# SCH_GROUP-8-WORK.net
KiCad netlist of a schematic drawn in EasyEDA
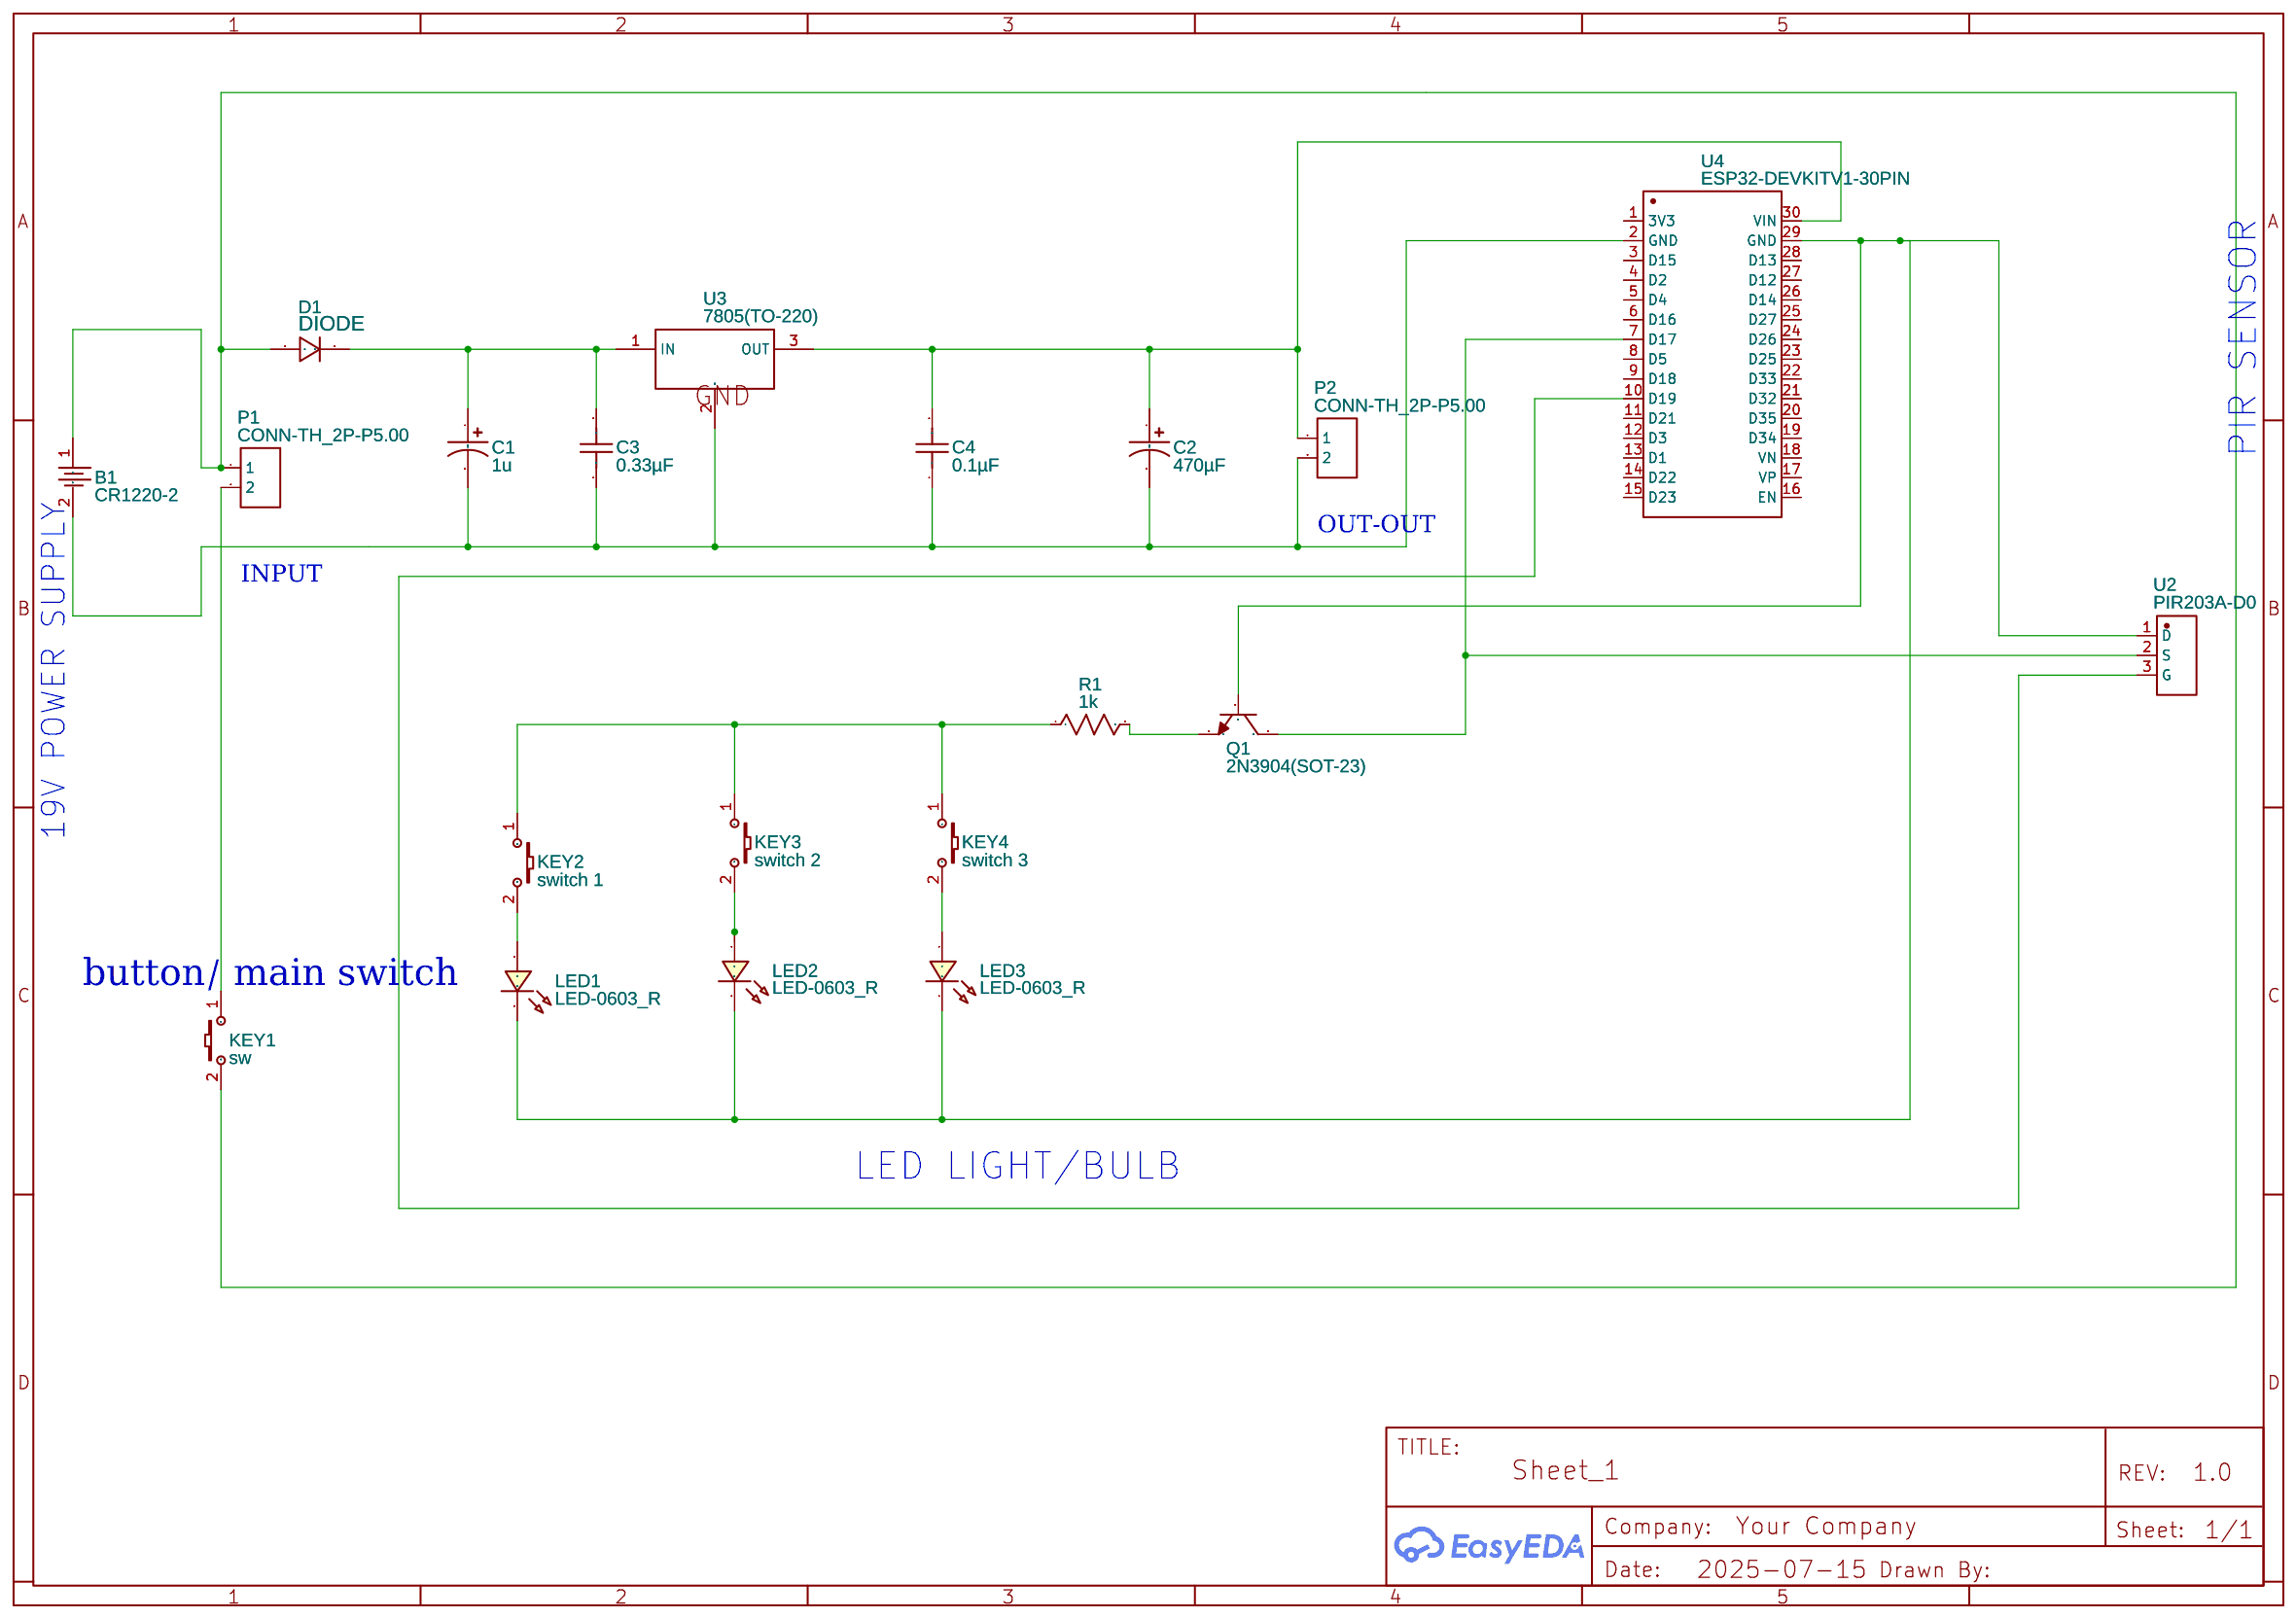
[diagram p0: schematic sheet]

(export (version "E")
  (design (tool "Eeschema 10.0.6"))
  (components
    (comp (ref "B1")
      (value "CR1220-2")
      (fields (field (name "Manufacturer") "Q&J"))
      (libsource (lib "") (part "CR1220-2"))
    )
    (comp (ref "C1") (value "1u") (libsource (lib "") (part "CE_TH_D3.0×F1.5_US")))
    (comp (ref "C2") (value "470µF") (libsource (lib "") (part "CE_TH_D3.0×F1.5_US")))
    (comp (ref "C3") (value "0.33µF") (libsource (lib "") (part "C_RAD-0.1_US")))
    (comp (ref "C4") (value "0.1µF") (libsource (lib "") (part "C_RAD-0.1_US")))
    (comp (ref "D1")
      (value "DIODE")
      (fields (field (name "Manufacturer Part") "1N4007W") (field (name "Manufacturer") "BLUE ROCKET"))
      (libsource (lib "") (part "1N4007W"))
    )
    (comp (ref "KEY1")
      (value "sw")
      (fields (field (name "Manufacturer Part") "K2-1107ST-A4SW-06"))
      (libsource (lib "") (part "K2-3.6×6.1_SMD_1"))
    )
    (comp (ref "KEY2")
      (value "switch 1")
      (fields (field (name "Manufacturer Part") "K2-1107ST-A4SW-06"))
      (libsource (lib "") (part "K2-3.6×6.1_SMD"))
    )
    (comp (ref "KEY3")
      (value "switch 2")
      (fields (field (name "Manufacturer Part") "K2-1107ST-A4SW-06"))
      (libsource (lib "") (part "K2-3.6×6.1_SMD"))
    )
    (comp (ref "KEY4")
      (value "switch 3")
      (fields (field (name "Manufacturer Part") "K2-1107ST-A4SW-06"))
      (libsource (lib "") (part "K2-3.6×6.1_SMD"))
    )
    (comp (ref "LED1")
      (value "LED-0603_R")
      (fields
        (field (name "Manufacturer Part") "19-217/R6C-AL1M2VY/3T")
        (field (name "Manufacturer") "EVERLIGHT(台湾亿光)")
      )
      (libsource (lib "") (part "LED-0603_R"))
    )
    (comp (ref "LED2")
      (value "LED-0603_R")
      (fields
        (field (name "Manufacturer Part") "19-217/R6C-AL1M2VY/3T")
        (field (name "Manufacturer") "EVERLIGHT(台湾亿光)")
      )
      (libsource (lib "") (part "LED-0603_R"))
    )
    (comp (ref "LED3")
      (value "LED-0603_R")
      (fields
        (field (name "Manufacturer Part") "19-217/R6C-AL1M2VY/3T")
        (field (name "Manufacturer") "EVERLIGHT(台湾亿光)")
      )
      (libsource (lib "") (part "LED-0603_R"))
    )
    (comp (ref "P1") (value "CONN-TH_2P-P5.00") (libsource (lib "") (part "CONN-TH_2P-P5.00")))
    (comp (ref "P2") (value "CONN-TH_2P-P5.00") (libsource (lib "") (part "CONN-TH_2P-P5.00")))
    (comp (ref "Q1")
      (value "2N3904(SOT-23)")
      (fields (field (name "Manufacturer Part") "2n3904S-RTK/PS") (field (name "Manufacturer") "KEC"))
      (libsource (lib "") (part "2N3904(SOT-23)"))
    )
    (comp (ref "R1") (value "1k") (libsource (lib "") (part "R_0603_US")))
    (comp (ref "U2")
      (value "PIR203A-D0")
      (fields (field (name "Manufacturer") "NEWOPTO(鑫永诚光电)"))
      (libsource (lib "") (part "PIR203A-D0"))
    )
    (comp (ref "U3")
      (value "7805(TO-220)")
      (fields
        (field (name "Manufacturer Part") "L7805CV-DG")
        (field (name "Manufacturer") "STMicroelectronics")
      )
      (libsource (lib "") (part "7805(TO-220)"))
    )
    (comp (ref "U4")
      (value "ESP32-DEVKITV1-30PIN")
      (fields
        (field (name "Manufacturer Part") "ESP32-DevKitV")
        (field (name "Manufacturer") "ESPRESSIF(乐鑫)")
      )
      (libsource (lib "") (part "ESP32-DEVKITV1-30PIN"))
    )
  )
  (nets
    (net (code "1") (name "Net-(B1-Pad1)") (class "Default")
      (node (ref "B1") (pin "1") (pinfunction "1_1") (pintype "input"))
      (node (ref "D1") (pin "2") (pinfunction "2_2") (pintype "unspecified"))
      (node (ref "KEY1") (pin "2") (pinfunction "2_2") (pintype "unspecified"))
      (node (ref "P1") (pin "1") (pinfunction "1_1") (pintype "unspecified"))
    )
    (net (code "2") (name "Net-(KEY1-Pad1)") (class "Default")
      (node (ref "KEY1") (pin "1") (pinfunction "1_1") (pintype "unspecified"))
      (node (ref "P1") (pin "2") (pinfunction "2_2") (pintype "unspecified"))
    )
    (net (code "3") (name "Net-(KEY2-Pad1)") (class "Default")
      (node (ref "KEY2") (pin "1") (pinfunction "1_1") (pintype "unspecified"))
      (node (ref "KEY3") (pin "1") (pinfunction "1_1") (pintype "unspecified"))
      (node (ref "KEY4") (pin "1") (pinfunction "1_1") (pintype "unspecified"))
      (node (ref "R1") (pin "1") (pinfunction "1_1") (pintype "unspecified"))
    )
    (net (code "4") (name "Net-(KEY2-Pad2)") (class "Default")
      (node (ref "KEY2") (pin "2") (pinfunction "2_2") (pintype "unspecified"))
      (node (ref "LED1") (pin "1") (pinfunction "1_1") (pintype "unspecified"))
    )
    (net (code "5") (name "Net-(KEY3-Pad2)") (class "Default")
      (node (ref "KEY3") (pin "2") (pinfunction "2_2") (pintype "unspecified"))
      (node (ref "LED2") (pin "1") (pinfunction "1_1") (pintype "unspecified"))
    )
    (net (code "6") (name "Net-(KEY4-Pad2)") (class "Default")
      (node (ref "KEY4") (pin "2") (pinfunction "2_2") (pintype "unspecified"))
      (node (ref "LED3") (pin "1") (pinfunction "1_1") (pintype "unspecified"))
    )
    (net (code "7") (name "Net-(Q1-B)") (class "Default")
      (node (ref "LED1") (pin "2") (pinfunction "2_2") (pintype "unspecified"))
      (node (ref "LED2") (pin "2") (pinfunction "2_2") (pintype "unspecified"))
      (node (ref "LED3") (pin "2") (pinfunction "2_2") (pintype "unspecified"))
      (node (ref "Q1") (pin "2") (pinfunction "B_2") (pintype "input"))
      (node (ref "U2") (pin "1") (pinfunction "D_1") (pintype "unspecified"))
      (node (ref "U4") (pin "29") (pinfunction "GND_29") (pintype "unspecified"))
    )
    (net (code "8") (name "Net-(Q1-C)") (class "Default")
      (node (ref "Q1") (pin "3") (pinfunction "C_3") (pintype "input"))
      (node (ref "U2") (pin "2") (pinfunction "S_2") (pintype "unspecified"))
      (node (ref "U4") (pin "7") (pinfunction "D17_7") (pintype "unspecified"))
    )
    (net (code "9") (name "Net-(Q1-E)") (class "Default")
      (node (ref "Q1") (pin "1") (pinfunction "E_1") (pintype "input"))
      (node (ref "R1") (pin "2") (pinfunction "2_2") (pintype "unspecified"))
    )
    (net (code "10") (name "Net-(U2-G)") (class "Default")
      (node (ref "U2") (pin "3") (pinfunction "G_3") (pintype "unspecified"))
      (node (ref "U4") (pin "10") (pinfunction "D19_10") (pintype "unspecified"))
    )
    (net (code "11") (name "Net-(U3-GND)") (class "Default")
      (node (ref "B1") (pin "2") (pinfunction "2_2") (pintype "input"))
      (node (ref "C1") (pin "2") (pinfunction "2_2") (pintype "unspecified"))
      (node (ref "C2") (pin "2") (pinfunction "2_2") (pintype "unspecified"))
      (node (ref "C3") (pin "1") (pinfunction "1_1") (pintype "unspecified"))
      (node (ref "C4") (pin "1") (pinfunction "1_1") (pintype "unspecified"))
      (node (ref "P2") (pin "2") (pinfunction "2_2") (pintype "unspecified"))
      (node (ref "U3") (pin "2") (pinfunction "GND_2") (pintype "passive"))
      (node (ref "U4") (pin "2") (pinfunction "GND_2") (pintype "unspecified"))
    )
    (net (code "12") (name "Net-(U3-IN)") (class "Default")
      (node (ref "C1") (pin "1") (pinfunction "1_1") (pintype "unspecified"))
      (node (ref "C3") (pin "2") (pinfunction "2_2") (pintype "unspecified"))
      (node (ref "D1") (pin "1") (pinfunction "1_1") (pintype "unspecified"))
      (node (ref "U3") (pin "1") (pinfunction "IN_1") (pintype "passive"))
    )
    (net (code "13") (name "Net-(U3-OUT)") (class "Default")
      (node (ref "C2") (pin "1") (pinfunction "1_1") (pintype "unspecified"))
      (node (ref "C4") (pin "2") (pinfunction "2_2") (pintype "unspecified"))
      (node (ref "P2") (pin "1") (pinfunction "1_1") (pintype "unspecified"))
      (node (ref "U3") (pin "3") (pinfunction "OUT_3") (pintype "passive"))
      (node (ref "U4") (pin "30") (pinfunction "VIN_30") (pintype "unspecified"))
    )
    (net (code "14") (name "unconnected-(U4-3V3-Pad1)") (class "Default")
      (node (ref "U4") (pin "1") (pinfunction "3V3_1") (pintype "unspecified"))
    )
    (net (code "15") (name "unconnected-(U4-D1-Pad13)") (class "Default")
      (node (ref "U4") (pin "13") (pinfunction "D1_13") (pintype "unspecified"))
    )
    (net (code "16") (name "unconnected-(U4-D2-Pad4)") (class "Default")
      (node (ref "U4") (pin "4") (pinfunction "D2_4") (pintype "unspecified"))
    )
    (net (code "17") (name "unconnected-(U4-D3-Pad12)") (class "Default")
      (node (ref "U4") (pin "12") (pinfunction "D3_12") (pintype "unspecified"))
    )
    (net (code "18") (name "unconnected-(U4-D4-Pad5)") (class "Default")
      (node (ref "U4") (pin "5") (pinfunction "D4_5") (pintype "unspecified"))
    )
    (net (code "19") (name "unconnected-(U4-D5-Pad8)") (class "Default")
      (node (ref "U4") (pin "8") (pinfunction "D5_8") (pintype "unspecified"))
    )
    (net (code "20") (name "unconnected-(U4-D12-Pad27)") (class "Default")
      (node (ref "U4") (pin "27") (pinfunction "D12_27") (pintype "unspecified"))
    )
    (net (code "21") (name "unconnected-(U4-D13-Pad28)") (class "Default")
      (node (ref "U4") (pin "28") (pinfunction "D13_28") (pintype "unspecified"))
    )
    (net (code "22") (name "unconnected-(U4-D14-Pad26)") (class "Default")
      (node (ref "U4") (pin "26") (pinfunction "D14_26") (pintype "unspecified"))
    )
    (net (code "23") (name "unconnected-(U4-D15-Pad3)") (class "Default")
      (node (ref "U4") (pin "3") (pinfunction "D15_3") (pintype "unspecified"))
    )
    (net (code "24") (name "unconnected-(U4-D16-Pad6)") (class "Default")
      (node (ref "U4") (pin "6") (pinfunction "D16_6") (pintype "unspecified"))
    )
    (net (code "25") (name "unconnected-(U4-D18-Pad9)") (class "Default")
      (node (ref "U4") (pin "9") (pinfunction "D18_9") (pintype "unspecified"))
    )
    (net (code "26") (name "unconnected-(U4-D21-Pad11)") (class "Default")
      (node (ref "U4") (pin "11") (pinfunction "D21_11") (pintype "unspecified"))
    )
    (net (code "27") (name "unconnected-(U4-D22-Pad14)") (class "Default")
      (node (ref "U4") (pin "14") (pinfunction "D22_14") (pintype "unspecified"))
    )
    (net (code "28") (name "unconnected-(U4-D23-Pad15)") (class "Default")
      (node (ref "U4") (pin "15") (pinfunction "D23_15") (pintype "unspecified"))
    )
    (net (code "29") (name "unconnected-(U4-D25-Pad23)") (class "Default")
      (node (ref "U4") (pin "23") (pinfunction "D25_23") (pintype "unspecified"))
    )
    (net (code "30") (name "unconnected-(U4-D26-Pad24)") (class "Default")
      (node (ref "U4") (pin "24") (pinfunction "D26_24") (pintype "unspecified"))
    )
    (net (code "31") (name "unconnected-(U4-D27-Pad25)") (class "Default")
      (node (ref "U4") (pin "25") (pinfunction "D27_25") (pintype "unspecified"))
    )
    (net (code "32") (name "unconnected-(U4-D32-Pad21)") (class "Default")
      (node (ref "U4") (pin "21") (pinfunction "D32_21") (pintype "unspecified"))
    )
    (net (code "33") (name "unconnected-(U4-D33-Pad22)") (class "Default")
      (node (ref "U4") (pin "22") (pinfunction "D33_22") (pintype "unspecified"))
    )
    (net (code "34") (name "unconnected-(U4-D34-Pad19)") (class "Default")
      (node (ref "U4") (pin "19") (pinfunction "D34_19") (pintype "unspecified"))
    )
    (net (code "35") (name "unconnected-(U4-D35-Pad20)") (class "Default")
      (node (ref "U4") (pin "20") (pinfunction "D35_20") (pintype "unspecified"))
    )
    (net (code "36") (name "unconnected-(U4-EN-Pad16)") (class "Default")
      (node (ref "U4") (pin "16") (pinfunction "EN_16") (pintype "unspecified"))
    )
    (net (code "37") (name "unconnected-(U4-VN-Pad18)") (class "Default")
      (node (ref "U4") (pin "18") (pinfunction "VN_18") (pintype "unspecified"))
    )
    (net (code "38") (name "unconnected-(U4-VP-Pad17)") (class "Default")
      (node (ref "U4") (pin "17") (pinfunction "VP_17") (pintype "unspecified"))
    )
  )
)
